# DRV8818_single_axis.net
KiCad netlist of a schematic drawn in EAGLE
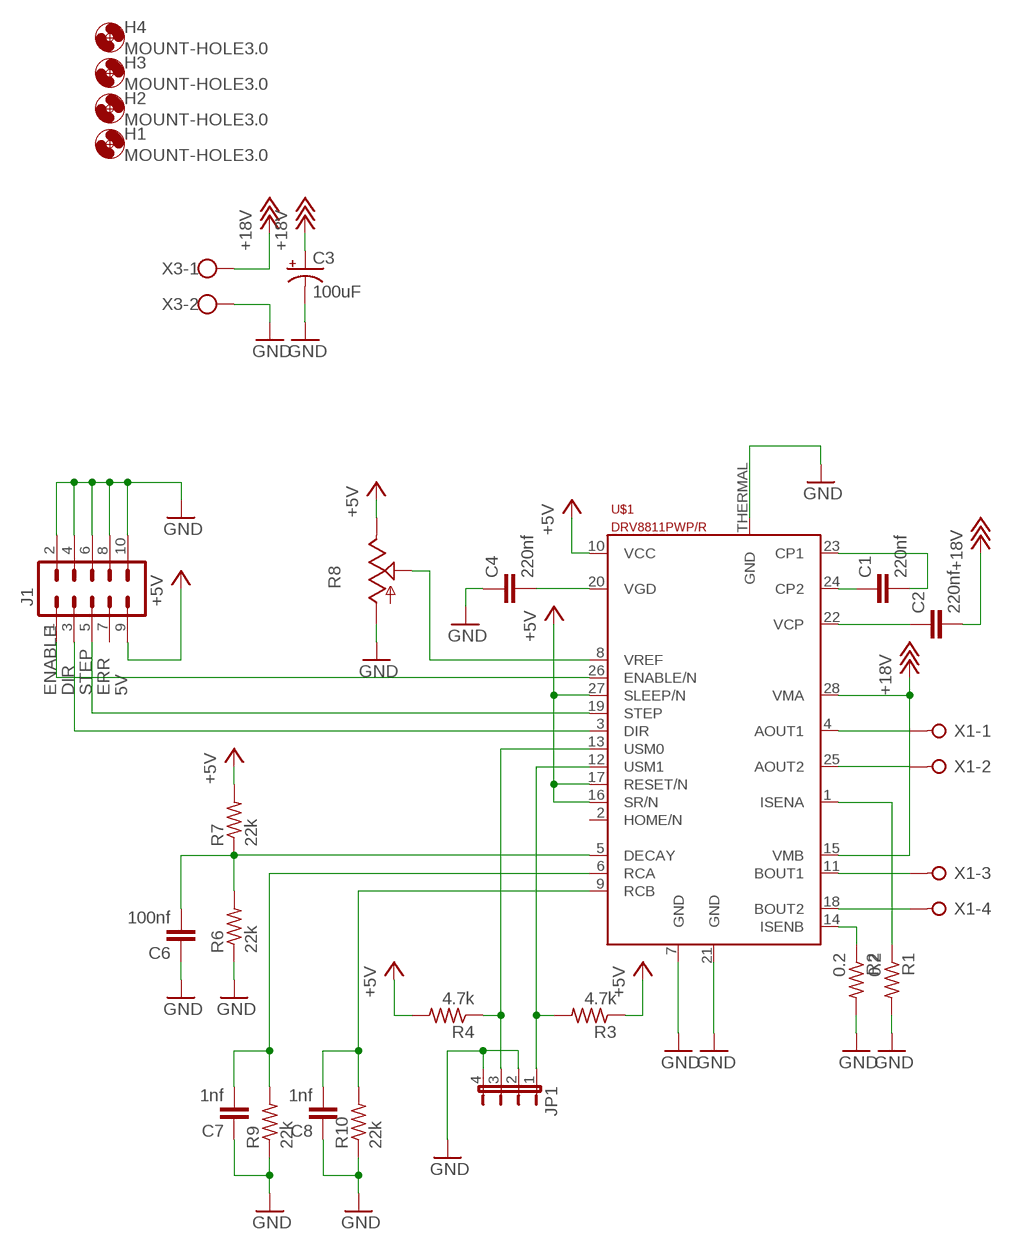
[diagram p0: schematic, sheet 1]

(export (version "E")
  (design (tool "Eeschema 10.0.6"))
  (components
    (comp (ref "C1")
      (value "220nf")
      (footprint "eagle-import:C1206")
      (libsource (lib "eagle-import") (part "C-EUC1206"))
    )
    (comp (ref "C2")
      (value "220nf")
      (footprint "eagle-import:C1206")
      (libsource (lib "eagle-import") (part "C-EUC1206"))
    )
    (comp (ref "C3")
      (value "100uF")
      (footprint "eagle-import:NIC_10X10.5_CAP")
      (libsource (lib "eagle-import") (part "100UF-63V-20%(ELECT)"))
    )
    (comp (ref "C4")
      (value "220nf")
      (footprint "eagle-import:C1206")
      (libsource (lib "eagle-import") (part "C-EUC1206"))
    )
    (comp (ref "C6")
      (value "100nf")
      (footprint "eagle-import:C1206")
      (libsource (lib "eagle-import") (part "C-EUC1206"))
    )
    (comp (ref "C7")
      (value "1nf")
      (footprint "eagle-import:C1206")
      (libsource (lib "eagle-import") (part "C-EUC1206"))
    )
    (comp (ref "C8")
      (value "1nf")
      (footprint "eagle-import:C1206")
      (libsource (lib "eagle-import") (part "C-EUC1206"))
    )
    (comp (ref "H1")
      (value "MOUNT-HOLE3.0")
      (footprint "eagle-import:3,0")
      (libsource (lib "eagle-import") (part "MOUNT-HOLE3.0"))
    )
    (comp (ref "H2")
      (value "MOUNT-HOLE3.0")
      (footprint "eagle-import:3,0")
      (libsource (lib "eagle-import") (part "MOUNT-HOLE3.0"))
    )
    (comp (ref "H3")
      (value "MOUNT-HOLE3.0")
      (footprint "eagle-import:3,0")
      (libsource (lib "eagle-import") (part "MOUNT-HOLE3.0"))
    )
    (comp (ref "H4")
      (value "MOUNT-HOLE3.0")
      (footprint "eagle-import:3,0")
      (libsource (lib "eagle-import") (part "MOUNT-HOLE3.0"))
    )
    (comp (ref "J1")
      (value "M05X2SHD_LOCK")
      (footprint "eagle-import:2X5-SHROUDED_LOCK")
      (libsource (lib "eagle-import") (part "M05X2SHD_LOCK"))
    )
    (comp (ref "JP1")
      (value "JP4E")
      (footprint "eagle-import:JP4")
      (libsource (lib "eagle-import") (part "JP4E"))
    )
    (comp (ref "R1")
      (value "0.2")
      (footprint "eagle-import:R2512")
      (libsource (lib "eagle-import") (part "R-US_R2512"))
    )
    (comp (ref "R2")
      (value "0.2")
      (footprint "eagle-import:R2512")
      (libsource (lib "eagle-import") (part "R-US_R2512"))
    )
    (comp (ref "R3")
      (value "4.7k")
      (footprint "eagle-import:R1206")
      (libsource (lib "eagle-import") (part "R-US_R1206"))
    )
    (comp (ref "R4")
      (value "4.7k")
      (footprint "eagle-import:R1206")
      (libsource (lib "eagle-import") (part "R-US_R1206"))
    )
    (comp (ref "R6")
      (value "22k")
      (footprint "eagle-import:R1206")
      (libsource (lib "eagle-import") (part "R-US_R1206"))
    )
    (comp (ref "R7")
      (value "22k")
      (footprint "eagle-import:R1206")
      (libsource (lib "eagle-import") (part "R-US_R1206"))
    )
    (comp (ref "R8")
      (value "TRIM_US-CA6V")
      (footprint "eagle-import:CA6V")
      (libsource (lib "eagle-import") (part "TRIM_US-CA6V"))
    )
    (comp (ref "R9")
      (value "22k")
      (footprint "eagle-import:R1206")
      (libsource (lib "eagle-import") (part "R-US_R1206"))
    )
    (comp (ref "R10")
      (value "22k")
      (footprint "eagle-import:R1206")
      (libsource (lib "eagle-import") (part "R-US_R1206"))
    )
    (comp (ref "U$1")
      (value "DRV8811PWP/R")
      (footprint "eagle-import:HTSSOP28")
      (fields (field (name "MF") "TEXAS INSTRUMENTS"))
      (libsource (lib "eagle-import") (part "DRV8811PWP/R"))
    )
    (comp (ref "X1")
      (value "W237-04P")
      (footprint "eagle-import:W237-4P")
      (libsource (lib "eagle-import") (part "W237-04P"))
    )
    (comp (ref "X3")
      (value "W237-102")
      (footprint "eagle-import:W237-102")
      (fields (field (name "MPN") "237-102"))
      (libsource (lib "eagle-import") (part "W237-102"))
    )
  )
  (nets
    (net (code "1") (name "+5V") (class "Default")
      (node (ref "J1") (pin "9") (pinfunction "9_9") (pintype "passive"))
      (node (ref "R3") (pin "1") (pinfunction "1_1") (pintype "passive"))
      (node (ref "R4") (pin "2") (pinfunction "2_2") (pintype "passive"))
      (node (ref "R7") (pin "2") (pinfunction "2_2") (pintype "passive"))
      (node (ref "R8") (pin "E") (pinfunction "E_E") (pintype "passive"))
      (node (ref "U$1") (pin "10") (pinfunction "VCC_10") (pintype "power_in"))
      (node (ref "U$1") (pin "16") (pinfunction "SR/N_16") (pintype "input"))
      (node (ref "U$1") (pin "17") (pinfunction "RESET/N_17") (pintype "input"))
      (node (ref "U$1") (pin "27") (pinfunction "SLEEP/N_27") (pintype "input"))
    )
    (net (code "2") (name "+18V") (class "Default")
      (node (ref "C2") (pin "2") (pinfunction "2_2") (pintype "passive"))
      (node (ref "C3") (pin "+") (pinfunction "+_+") (pintype "passive"))
      (node (ref "U$1") (pin "15") (pinfunction "VMB_15") (pintype "power_in"))
      (node (ref "U$1") (pin "28") (pinfunction "VMA_28") (pintype "power_in"))
      (node (ref "X3") (pin "1") (pinfunction "KL_1") (pintype "passive"))
    )
    (net (code "3") (name "GND") (class "Default")
      (node (ref "C3") (pin "-") (pinfunction "-_-") (pintype "passive"))
      (node (ref "C4") (pin "1") (pinfunction "1_1") (pintype "passive"))
      (node (ref "C6") (pin "1") (pinfunction "1_1") (pintype "passive"))
      (node (ref "C7") (pin "1") (pinfunction "1_1") (pintype "passive"))
      (node (ref "C8") (pin "1") (pinfunction "1_1") (pintype "passive"))
      (node (ref "J1") (pin "10") (pinfunction "10_10") (pintype "passive"))
      (node (ref "J1") (pin "2") (pinfunction "2_2") (pintype "passive"))
      (node (ref "J1") (pin "4") (pinfunction "4_4") (pintype "passive"))
      (node (ref "J1") (pin "6") (pinfunction "6_6") (pintype "passive"))
      (node (ref "J1") (pin "8") (pinfunction "8_8") (pintype "passive"))
      (node (ref "JP1") (pin "2") (pinfunction "2_2") (pintype "passive"))
      (node (ref "JP1") (pin "4") (pinfunction "4_4") (pintype "passive"))
      (node (ref "R1") (pin "2") (pinfunction "2_2") (pintype "passive"))
      (node (ref "R10") (pin "1") (pinfunction "1_1") (pintype "passive"))
      (node (ref "R2") (pin "2") (pinfunction "2_2") (pintype "passive"))
      (node (ref "R6") (pin "1") (pinfunction "1_1") (pintype "passive"))
      (node (ref "R8") (pin "A") (pinfunction "A_A") (pintype "passive"))
      (node (ref "R9") (pin "1") (pinfunction "1_1") (pintype "passive"))
      (node (ref "U$1") (pin "21") (pinfunction "GND_21") (pintype "power_in"))
      (node (ref "U$1") (pin "7") (pinfunction "GND_7") (pintype "power_in"))
      (node (ref "U$1") (pin "THERMAL") (pinfunction "GND_THERMAL") (pintype "power_in"))
      (node (ref "X3") (pin "2") (pinfunction "KL_2") (pintype "passive"))
    )
    (net (code "4") (name "Net-(U$1-AOUT1)") (class "Default")
      (node (ref "U$1") (pin "4") (pinfunction "AOUT1_4") (pintype "output"))
      (node (ref "X1") (pin "1") (pinfunction "KL_1") (pintype "passive"))
    )
    (net (code "5") (name "Net-(U$1-AOUT2)") (class "Default")
      (node (ref "U$1") (pin "25") (pinfunction "AOUT2_25") (pintype "output"))
      (node (ref "X1") (pin "2") (pinfunction "KL_2") (pintype "passive"))
    )
    (net (code "6") (name "Net-(U$1-BOUT1)") (class "Default")
      (node (ref "U$1") (pin "11") (pinfunction "BOUT1_11") (pintype "output"))
      (node (ref "X1") (pin "3") (pinfunction "KL_3") (pintype "passive"))
    )
    (net (code "7") (name "Net-(U$1-BOUT2)") (class "Default")
      (node (ref "U$1") (pin "18") (pinfunction "BOUT2_18") (pintype "output"))
      (node (ref "X1") (pin "4") (pinfunction "KL_4") (pintype "passive"))
    )
    (net (code "8") (name "Net-(U$1-CP1)") (class "Default")
      (node (ref "C1") (pin "2") (pinfunction "2_2") (pintype "passive"))
      (node (ref "U$1") (pin "23") (pinfunction "CP1_23") (pintype "bidirectional"))
    )
    (net (code "9") (name "Net-(U$1-CP2)") (class "Default")
      (node (ref "C1") (pin "1") (pinfunction "1_1") (pintype "passive"))
      (node (ref "U$1") (pin "24") (pinfunction "CP2_24") (pintype "bidirectional"))
    )
    (net (code "10") (name "Net-(U$1-DECAY)") (class "Default")
      (node (ref "C6") (pin "2") (pinfunction "2_2") (pintype "passive"))
      (node (ref "R6") (pin "2") (pinfunction "2_2") (pintype "passive"))
      (node (ref "R7") (pin "1") (pinfunction "1_1") (pintype "passive"))
      (node (ref "U$1") (pin "5") (pinfunction "DECAY_5") (pintype "input"))
    )
    (net (code "11") (name "Net-(U$1-DIR)") (class "Default")
      (node (ref "J1") (pin "3") (pinfunction "3_3") (pintype "passive"))
      (node (ref "U$1") (pin "3") (pinfunction "DIR_3") (pintype "input"))
    )
    (net (code "12") (name "Net-(U$1-ENABLE{slash}N)") (class "Default")
      (node (ref "J1") (pin "1") (pinfunction "1_1") (pintype "passive"))
      (node (ref "U$1") (pin "26") (pinfunction "ENABLE/N_26") (pintype "input"))
    )
    (net (code "13") (name "Net-(U$1-ISENA)") (class "Default")
      (node (ref "R1") (pin "1") (pinfunction "1_1") (pintype "passive"))
      (node (ref "U$1") (pin "1") (pinfunction "ISENA_1") (pintype "power_in"))
    )
    (net (code "14") (name "Net-(U$1-ISENB)") (class "Default")
      (node (ref "R2") (pin "1") (pinfunction "1_1") (pintype "passive"))
      (node (ref "U$1") (pin "14") (pinfunction "ISENB_14") (pintype "power_in"))
    )
    (net (code "15") (name "Net-(U$1-RCA)") (class "Default")
      (node (ref "C7") (pin "2") (pinfunction "2_2") (pintype "passive"))
      (node (ref "R9") (pin "2") (pinfunction "2_2") (pintype "passive"))
      (node (ref "U$1") (pin "6") (pinfunction "RCA_6") (pintype "input"))
    )
    (net (code "16") (name "Net-(U$1-RCB)") (class "Default")
      (node (ref "C8") (pin "2") (pinfunction "2_2") (pintype "passive"))
      (node (ref "R10") (pin "2") (pinfunction "2_2") (pintype "passive"))
      (node (ref "U$1") (pin "9") (pinfunction "RCB_9") (pintype "input"))
    )
    (net (code "17") (name "Net-(U$1-STEP)") (class "Default")
      (node (ref "J1") (pin "5") (pinfunction "5_5") (pintype "passive"))
      (node (ref "U$1") (pin "19") (pinfunction "STEP_19") (pintype "input"))
    )
    (net (code "18") (name "Net-(U$1-USM0)") (class "Default")
      (node (ref "JP1") (pin "3") (pinfunction "3_3") (pintype "passive"))
      (node (ref "R4") (pin "1") (pinfunction "1_1") (pintype "passive"))
      (node (ref "U$1") (pin "13") (pinfunction "USM0_13") (pintype "input"))
    )
    (net (code "19") (name "Net-(U$1-USM1)") (class "Default")
      (node (ref "JP1") (pin "1") (pinfunction "1_1") (pintype "passive"))
      (node (ref "R3") (pin "2") (pinfunction "2_2") (pintype "passive"))
      (node (ref "U$1") (pin "12") (pinfunction "USM1_12") (pintype "input"))
    )
    (net (code "20") (name "Net-(U$1-VCP)") (class "Default")
      (node (ref "C2") (pin "1") (pinfunction "1_1") (pintype "passive"))
      (node (ref "U$1") (pin "22") (pinfunction "VCP_22") (pintype "bidirectional"))
    )
    (net (code "21") (name "Net-(U$1-VGD)") (class "Default")
      (node (ref "C4") (pin "2") (pinfunction "2_2") (pintype "passive"))
      (node (ref "U$1") (pin "20") (pinfunction "VGD_20") (pintype "bidirectional"))
    )
    (net (code "22") (name "Net-(U$1-VREF)") (class "Default")
      (node (ref "R8") (pin "S") (pinfunction "S_S") (pintype "passive"))
      (node (ref "U$1") (pin "8") (pinfunction "VREF_8") (pintype "input"))
    )
    (net (code "23") (name "unconnected-(J1-Pad7)") (class "Default")
      (node (ref "J1") (pin "7") (pinfunction "7_7") (pintype "passive"))
    )
    (net (code "24") (name "unconnected-(U$1-HOME{slash}N-Pad2)") (class "Default")
      (node (ref "U$1") (pin "2") (pinfunction "HOME/N_2") (pintype "output"))
    )
  )
)
